# Sensors.net
KiCad netlist of a schematic drawn in Altium Designer
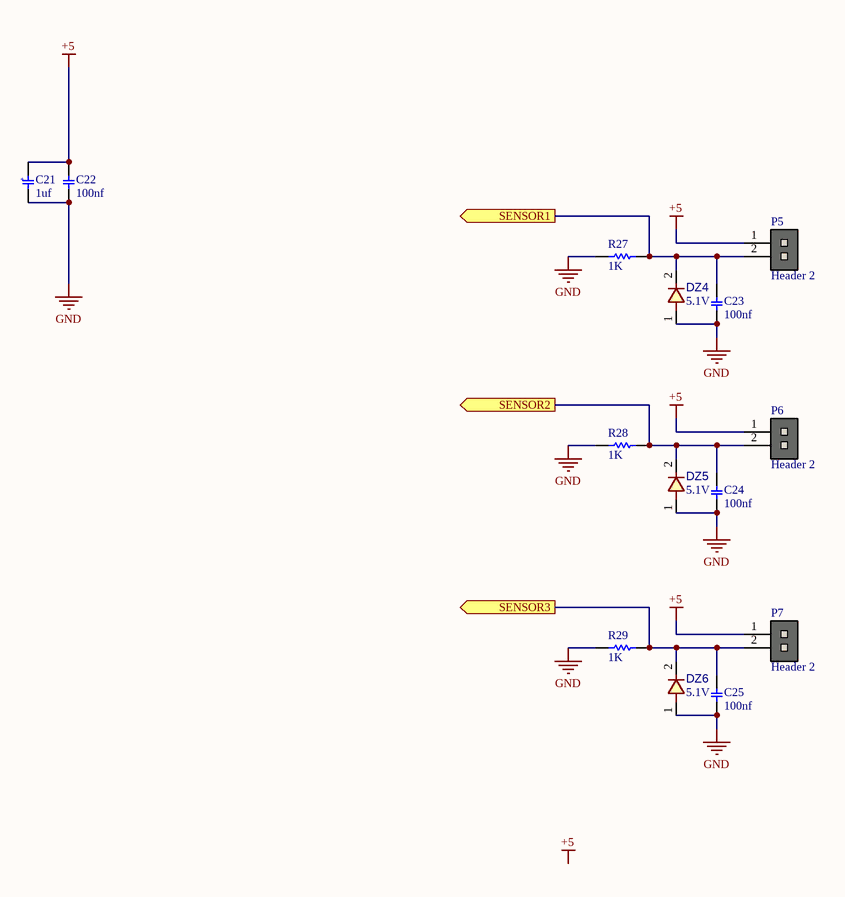
[diagram p0: Sensors.SchDoc]

(export (version "E")
  (design (tool "Eeschema 10.0.6"))
  (components
    (comp (ref "C21")
      (value "1uf")
      (footprint "C_EL_4X7")
      (description "Capacitor Electrical THD")
      (libsource (lib "Capacitor") (part "Capacitor Electrical THD"))
    )
    (comp (ref "C22")
      (value "100nf")
      (footprint "C1206")
      (description "Capacitor C SMD 1206")
      (libsource (lib "Capacitor") (part "Capacitor C SMD 1206"))
    )
    (comp (ref "C23")
      (value "100nf")
      (footprint "C1206")
      (description "Capacitor C SMD 1206")
      (libsource (lib "Capacitor") (part "Capacitor C SMD 1206"))
    )
    (comp (ref "C24")
      (value "100nf")
      (footprint "C1206")
      (description "Capacitor C SMD 1206")
      (libsource (lib "Capacitor") (part "Capacitor C SMD 1206"))
    )
    (comp (ref "C25")
      (value "100nf")
      (footprint "C1206")
      (description "Capacitor C SMD 1206")
      (libsource (lib "Capacitor") (part "Capacitor C SMD 1206"))
    )
    (comp (ref "DZ4")
      (value "5.1V")
      (footprint "D_SOD80")
      (description "DIODE, FAST SWTICHING, 0.3A, 0.5W")
      (fields (field (name "Comment") "1N4148 SMD"))
      (libsource (lib "Diode") (part "1N4148 SMD"))
    )
    (comp (ref "DZ5")
      (value "5.1V")
      (footprint "D_SOD80")
      (description "DIODE, FAST SWTICHING, 0.3A, 0.5W")
      (fields (field (name "Comment") "1N4148 SMD"))
      (libsource (lib "Diode") (part "1N4148 SMD"))
    )
    (comp (ref "DZ6")
      (value "5.1V")
      (footprint "D_SOD80")
      (description "DIODE, FAST SWTICHING, 0.3A, 0.5W")
      (fields (field (name "Comment") "1N4148 SMD"))
      (libsource (lib "Diode") (part "1N4148 SMD"))
    )
    (comp (ref "P5")
      (value "Header 2")
      (footprint "HDR 1X2")
      (description "Header, 2-Pin")
      (libsource (lib "Header") (part "Header 2"))
    )
    (comp (ref "P6")
      (value "Header 2")
      (footprint "HDR 1X2")
      (description "Header, 2-Pin")
      (libsource (lib "Header") (part "Header 2"))
    )
    (comp (ref "P7")
      (value "Header 2")
      (footprint "HDR 1X2")
      (description "Header, 2-Pin")
      (libsource (lib "Header") (part "Header 2"))
    )
    (comp (ref "R27")
      (value "1K")
      (footprint "SMD-1206-RES")
      (description "Resistor SMD 1206")
      (libsource (lib "Resistor") (part "Resistor SMD 1206"))
    )
    (comp (ref "R28")
      (value "1K")
      (footprint "SMD-1206-RES")
      (description "Resistor SMD 1206")
      (libsource (lib "Resistor") (part "Resistor SMD 1206"))
    )
    (comp (ref "R29")
      (value "1K")
      (footprint "SMD-1206-RES")
      (description "Resistor SMD 1206")
      (libsource (lib "Resistor") (part "Resistor SMD 1206"))
    )
  )
  (nets
    (net (code "1") (name "+5") (class "Default")
      (node (ref "C21") (pin "1") (pinfunction "1_1") (pintype "passive"))
      (node (ref "C22") (pin "2") (pinfunction "2_2") (pintype "passive"))
      (node (ref "P5") (pin "1") (pinfunction "1_1") (pintype "passive"))
      (node (ref "P6") (pin "1") (pinfunction "1_1") (pintype "passive"))
      (node (ref "P7") (pin "1") (pinfunction "1_1") (pintype "passive"))
    )
    (net (code "2") (name "/SENSOR1") (class "Default")
      (node (ref "C23") (pin "2") (pinfunction "2_2") (pintype "passive"))
      (node (ref "DZ4") (pin "2") (pinfunction "2_2") (pintype "passive"))
      (node (ref "P5") (pin "2") (pinfunction "2_2") (pintype "passive"))
      (node (ref "R27") (pin "2") (pinfunction "2_2") (pintype "passive"))
    )
    (net (code "3") (name "/SENSOR2") (class "Default")
      (node (ref "C24") (pin "2") (pinfunction "2_2") (pintype "passive"))
      (node (ref "DZ5") (pin "2") (pinfunction "2_2") (pintype "passive"))
      (node (ref "P6") (pin "2") (pinfunction "2_2") (pintype "passive"))
      (node (ref "R28") (pin "2") (pinfunction "2_2") (pintype "passive"))
    )
    (net (code "4") (name "/SENSOR3") (class "Default")
      (node (ref "C25") (pin "2") (pinfunction "2_2") (pintype "passive"))
      (node (ref "DZ6") (pin "2") (pinfunction "2_2") (pintype "passive"))
      (node (ref "P7") (pin "2") (pinfunction "2_2") (pintype "passive"))
      (node (ref "R29") (pin "2") (pinfunction "2_2") (pintype "passive"))
    )
    (net (code "5") (name "GND") (class "Default")
      (node (ref "C21") (pin "2") (pinfunction "2_2") (pintype "passive"))
      (node (ref "C22") (pin "1") (pinfunction "1_1") (pintype "passive"))
      (node (ref "C23") (pin "1") (pinfunction "1_1") (pintype "passive"))
      (node (ref "C24") (pin "1") (pinfunction "1_1") (pintype "passive"))
      (node (ref "C25") (pin "1") (pinfunction "1_1") (pintype "passive"))
      (node (ref "DZ4") (pin "1") (pinfunction "1_1") (pintype "passive"))
      (node (ref "DZ5") (pin "1") (pinfunction "1_1") (pintype "passive"))
      (node (ref "DZ6") (pin "1") (pinfunction "1_1") (pintype "passive"))
      (node (ref "R27") (pin "1") (pinfunction "1_1") (pintype "passive"))
      (node (ref "R28") (pin "1") (pinfunction "1_1") (pintype "passive"))
      (node (ref "R29") (pin "1") (pinfunction "1_1") (pintype "passive"))
    )
  )
)
